# refgen.net
KiCad netlist of a schematic drawn in EAGLE
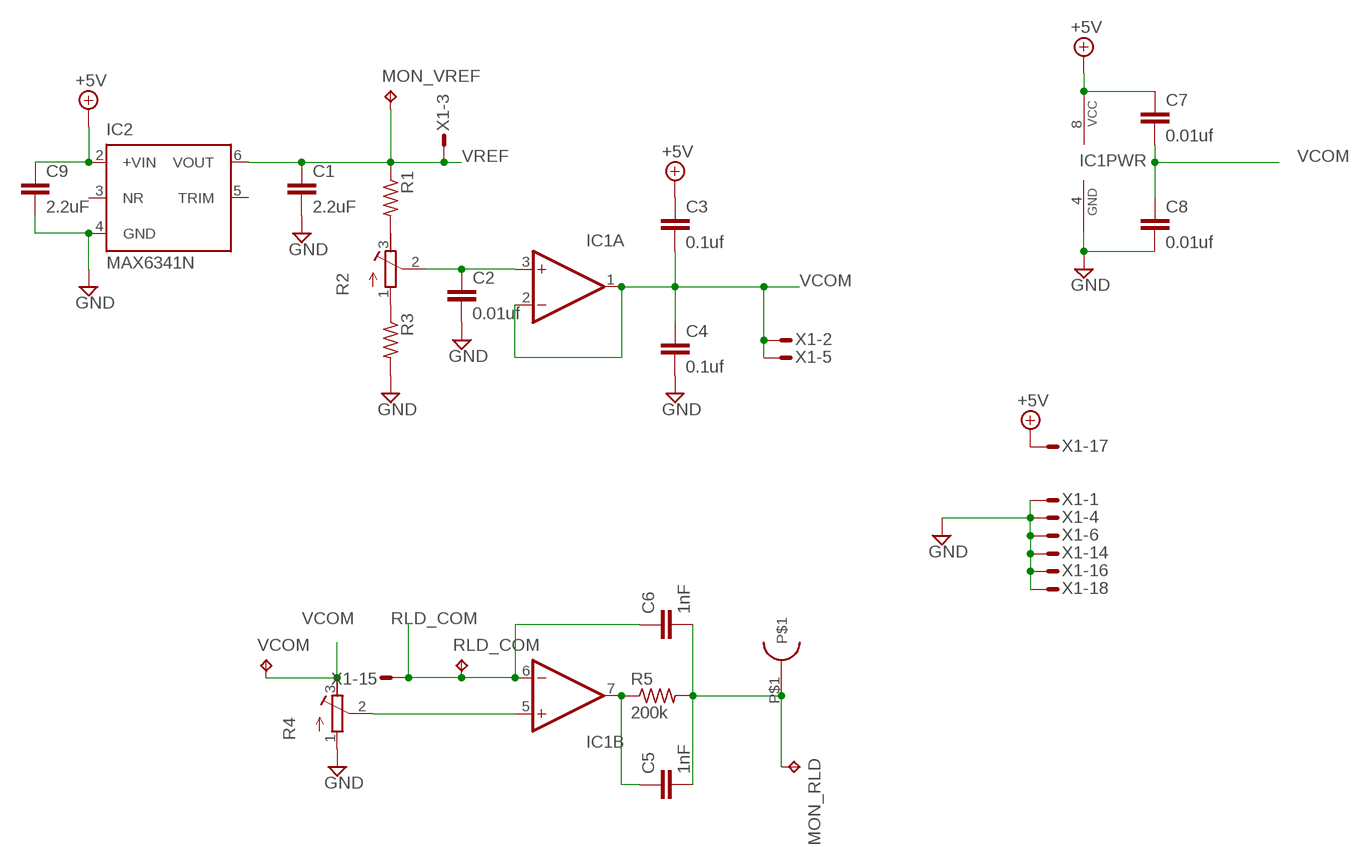
[diagram p0: schematic, sheet 1]

(export (version "E")
  (design (tool "Eeschema 10.0.6"))
  (components
    (comp (ref "C1")
      (value "2.2uF")
      (footprint "eagle-import:C050-025X075")
      (libsource (lib "eagle-import") (part "C-EU050-025X075"))
    )
    (comp (ref "C2")
      (value "0.01uf")
      (footprint "eagle-import:C050-025X075")
      (libsource (lib "eagle-import") (part "C-EU050-025X075"))
    )
    (comp (ref "C3")
      (value "0.1uf")
      (footprint "eagle-import:C050-025X075")
      (libsource (lib "eagle-import") (part "C-EU050-025X075"))
    )
    (comp (ref "C4")
      (value "0.1uf")
      (footprint "eagle-import:C050-025X075")
      (libsource (lib "eagle-import") (part "C-EU050-025X075"))
    )
    (comp (ref "C5")
      (value "1nF")
      (footprint "eagle-import:C050-025X075")
      (libsource (lib "eagle-import") (part "C-EU050-025X075"))
    )
    (comp (ref "C6")
      (value "1nF")
      (footprint "eagle-import:C050-025X075")
      (libsource (lib "eagle-import") (part "C-EU050-025X075"))
    )
    (comp (ref "C7")
      (value "0.01uf")
      (footprint "eagle-import:C050-025X075")
      (libsource (lib "eagle-import") (part "C-EU050-025X075"))
    )
    (comp (ref "C8")
      (value "0.01uf")
      (footprint "eagle-import:C050-025X075")
      (libsource (lib "eagle-import") (part "C-EU050-025X075"))
    )
    (comp (ref "C9")
      (value "2.2uF")
      (footprint "eagle-import:C050-025X075")
      (libsource (lib "eagle-import") (part "C-EU050-025X075"))
    )
    (comp (ref "IC1")
      (value "TLC277P")
      (footprint "eagle-import:DIL-08")
      (libsource (lib "eagle-import") (part "TLC277P"))
    )
    (comp (ref "IC2")
      (value "MAX6341N")
      (footprint "eagle-import:DIL08")
      (fields (field (name "MF") "ALTERA CORPORATION") (field (name "MPN") "AD780ANZ"))
      (libsource (lib "eagle-import") (part "MAX6341N"))
    )
    (comp (ref "MON_RLD")
      (value "TPPAD1-17")
      (footprint "eagle-import:P1-17")
      (libsource (lib "eagle-import") (part "TPPAD1-17"))
    )
    (comp (ref "MON_VREF")
      (value "TPPAD1-17")
      (footprint "eagle-import:P1-17")
      (libsource (lib "eagle-import") (part "TPPAD1-17"))
    )
    (comp (ref "R1")
      (value "R-US_0204/2V")
      (footprint "eagle-import:0204V")
      (libsource (lib "eagle-import") (part "R-US_0204/2V"))
    )
    (comp (ref "R2")
      (value "R-TRIMM3296W")
      (footprint "eagle-import:RTRIM3296W")
      (libsource (lib "eagle-import") (part "R-TRIMM3296W"))
    )
    (comp (ref "R3")
      (value "R-US_0204/2V")
      (footprint "eagle-import:0204V")
      (libsource (lib "eagle-import") (part "R-US_0204/2V"))
    )
    (comp (ref "R4")
      (value "R-TRIMM3296W")
      (footprint "eagle-import:RTRIM3296W")
      (libsource (lib "eagle-import") (part "R-TRIMM3296W"))
    )
    (comp (ref "R5")
      (value "200k")
      (footprint "eagle-import:0204V")
      (libsource (lib "eagle-import") (part "R-US_0204/2V"))
    )
    (comp (ref "RLD_COM")
      (value "TPPAD1-17")
      (footprint "eagle-import:P1-17")
      (libsource (lib "eagle-import") (part "TPPAD1-17"))
    )
    (comp (ref "RLD_OUT")
      (value "DIN42802")
      (footprint "eagle-import:DIN42802")
      (libsource (lib "eagle-import") (part "DIN42802"))
    )
    (comp (ref "VCOM")
      (value "TPPAD1-17")
      (footprint "eagle-import:P1-17")
      (libsource (lib "eagle-import") (part "TPPAD1-17"))
    )
    (comp (ref "X1")
      (value "M25HPS")
      (footprint "eagle-import:M25HP")
      (libsource (lib "eagle-import") (part "M25?SHP"))
    )
  )
  (nets
    (net (code "1") (name "+5V") (class "Default")
      (node (ref "C3") (pin "1") (pinfunction "1_1") (pintype "passive"))
      (node (ref "C7") (pin "1") (pinfunction "1_1") (pintype "passive"))
      (node (ref "C9") (pin "1") (pinfunction "1_1") (pintype "passive"))
      (node (ref "IC1") (pin "8") (pinfunction "VCC_8") (pintype "power_in"))
      (node (ref "IC2") (pin "2") (pinfunction "+VIN_2") (pintype "input"))
      (node (ref "X1") (pin "17") (pinfunction "M_17") (pintype "passive"))
    )
    (net (code "2") (name "/RLD_COM") (class "Default")
      (node (ref "C6") (pin "1") (pinfunction "1_1") (pintype "passive"))
      (node (ref "IC1") (pin "6") (pinfunction "-IN_6") (pintype "input"))
      (node (ref "RLD_COM") (pin "TP") (pinfunction "TP_TP") (pintype "input"))
      (node (ref "X1") (pin "15") (pinfunction "M_15") (pintype "passive"))
    )
    (net (code "3") (name "/VCOM") (class "Default")
      (node (ref "C3") (pin "2") (pinfunction "2_2") (pintype "passive"))
      (node (ref "C4") (pin "1") (pinfunction "1_1") (pintype "passive"))
      (node (ref "C7") (pin "2") (pinfunction "2_2") (pintype "passive"))
      (node (ref "C8") (pin "1") (pinfunction "1_1") (pintype "passive"))
      (node (ref "IC1") (pin "1") (pinfunction "OUT_1") (pintype "output"))
      (node (ref "IC1") (pin "2") (pinfunction "-IN_2") (pintype "input"))
      (node (ref "R4") (pin "3") (pinfunction "E_3") (pintype "passive"))
      (node (ref "VCOM") (pin "TP") (pinfunction "TP_TP") (pintype "input"))
      (node (ref "X1") (pin "2") (pinfunction "M_2") (pintype "passive"))
      (node (ref "X1") (pin "5") (pinfunction "M_5") (pintype "passive"))
    )
    (net (code "4") (name "/VREF") (class "Default")
      (node (ref "C1") (pin "1") (pinfunction "1_1") (pintype "passive"))
      (node (ref "IC2") (pin "6") (pinfunction "VOUT_6") (pintype "input"))
      (node (ref "MON_VREF") (pin "TP") (pinfunction "TP_TP") (pintype "input"))
      (node (ref "R1") (pin "1") (pinfunction "1_1") (pintype "passive"))
      (node (ref "X1") (pin "3") (pinfunction "M_3") (pintype "passive"))
    )
    (net (code "5") (name "GND") (class "Default")
      (node (ref "C1") (pin "2") (pinfunction "2_2") (pintype "passive"))
      (node (ref "C2") (pin "2") (pinfunction "2_2") (pintype "passive"))
      (node (ref "C4") (pin "2") (pinfunction "2_2") (pintype "passive"))
      (node (ref "C8") (pin "2") (pinfunction "2_2") (pintype "passive"))
      (node (ref "C9") (pin "2") (pinfunction "2_2") (pintype "passive"))
      (node (ref "IC1") (pin "4") (pinfunction "GND_4") (pintype "power_in"))
      (node (ref "IC2") (pin "4") (pinfunction "GND_4") (pintype "power_in"))
      (node (ref "R3") (pin "2") (pinfunction "2_2") (pintype "passive"))
      (node (ref "R4") (pin "1") (pinfunction "A_1") (pintype "passive"))
      (node (ref "X1") (pin "1") (pinfunction "M_1") (pintype "passive"))
      (node (ref "X1") (pin "14") (pinfunction "M_14") (pintype "passive"))
      (node (ref "X1") (pin "16") (pinfunction "M_16") (pintype "passive"))
      (node (ref "X1") (pin "18") (pinfunction "M_18") (pintype "passive"))
      (node (ref "X1") (pin "4") (pinfunction "M_4") (pintype "passive"))
      (node (ref "X1") (pin "6") (pinfunction "M_6") (pintype "passive"))
    )
    (net (code "6") (name "Net-(C5-Pad2)") (class "Default")
      (node (ref "C5") (pin "2") (pinfunction "2_2") (pintype "passive"))
      (node (ref "C6") (pin "2") (pinfunction "2_2") (pintype "passive"))
      (node (ref "MON_RLD") (pin "TP") (pinfunction "TP_TP") (pintype "input"))
      (node (ref "R5") (pin "2") (pinfunction "2_2") (pintype "passive"))
      (node (ref "RLD_OUT") (pin "P$1") (pinfunction "P$1_P$1") (pintype "bidirectional"))
    )
    (net (code "7") (name "Net-(IC1A-+IN)") (class "Default")
      (node (ref "C2") (pin "1") (pinfunction "1_1") (pintype "passive"))
      (node (ref "IC1") (pin "3") (pinfunction "+IN_3") (pintype "input"))
      (node (ref "R2") (pin "2") (pinfunction "S_2") (pintype "passive"))
    )
    (net (code "8") (name "Net-(IC1B-+IN)") (class "Default")
      (node (ref "IC1") (pin "5") (pinfunction "+IN_5") (pintype "input"))
      (node (ref "R4") (pin "2") (pinfunction "S_2") (pintype "passive"))
    )
    (net (code "9") (name "Net-(IC1B-OUT)") (class "Default")
      (node (ref "C5") (pin "1") (pinfunction "1_1") (pintype "passive"))
      (node (ref "IC1") (pin "7") (pinfunction "OUT_7") (pintype "output"))
      (node (ref "R5") (pin "1") (pinfunction "1_1") (pintype "passive"))
    )
    (net (code "10") (name "Net-(R2-A)") (class "Default")
      (node (ref "R2") (pin "1") (pinfunction "A_1") (pintype "passive"))
      (node (ref "R3") (pin "1") (pinfunction "1_1") (pintype "passive"))
    )
    (net (code "11") (name "Net-(R2-E)") (class "Default")
      (node (ref "R1") (pin "2") (pinfunction "2_2") (pintype "passive"))
      (node (ref "R2") (pin "3") (pinfunction "E_3") (pintype "passive"))
    )
    (net (code "12") (name "unconnected-(IC2-NR-Pad3)") (class "Default")
      (node (ref "IC2") (pin "3") (pinfunction "NR_3") (pintype "input"))
    )
    (net (code "13") (name "unconnected-(IC2-TRIM-Pad5)") (class "Default")
      (node (ref "IC2") (pin "5") (pinfunction "TRIM_5") (pintype "input"))
    )
  )
)
